# PC2CAN.net
KiCad netlist of a schematic drawn in EAGLE
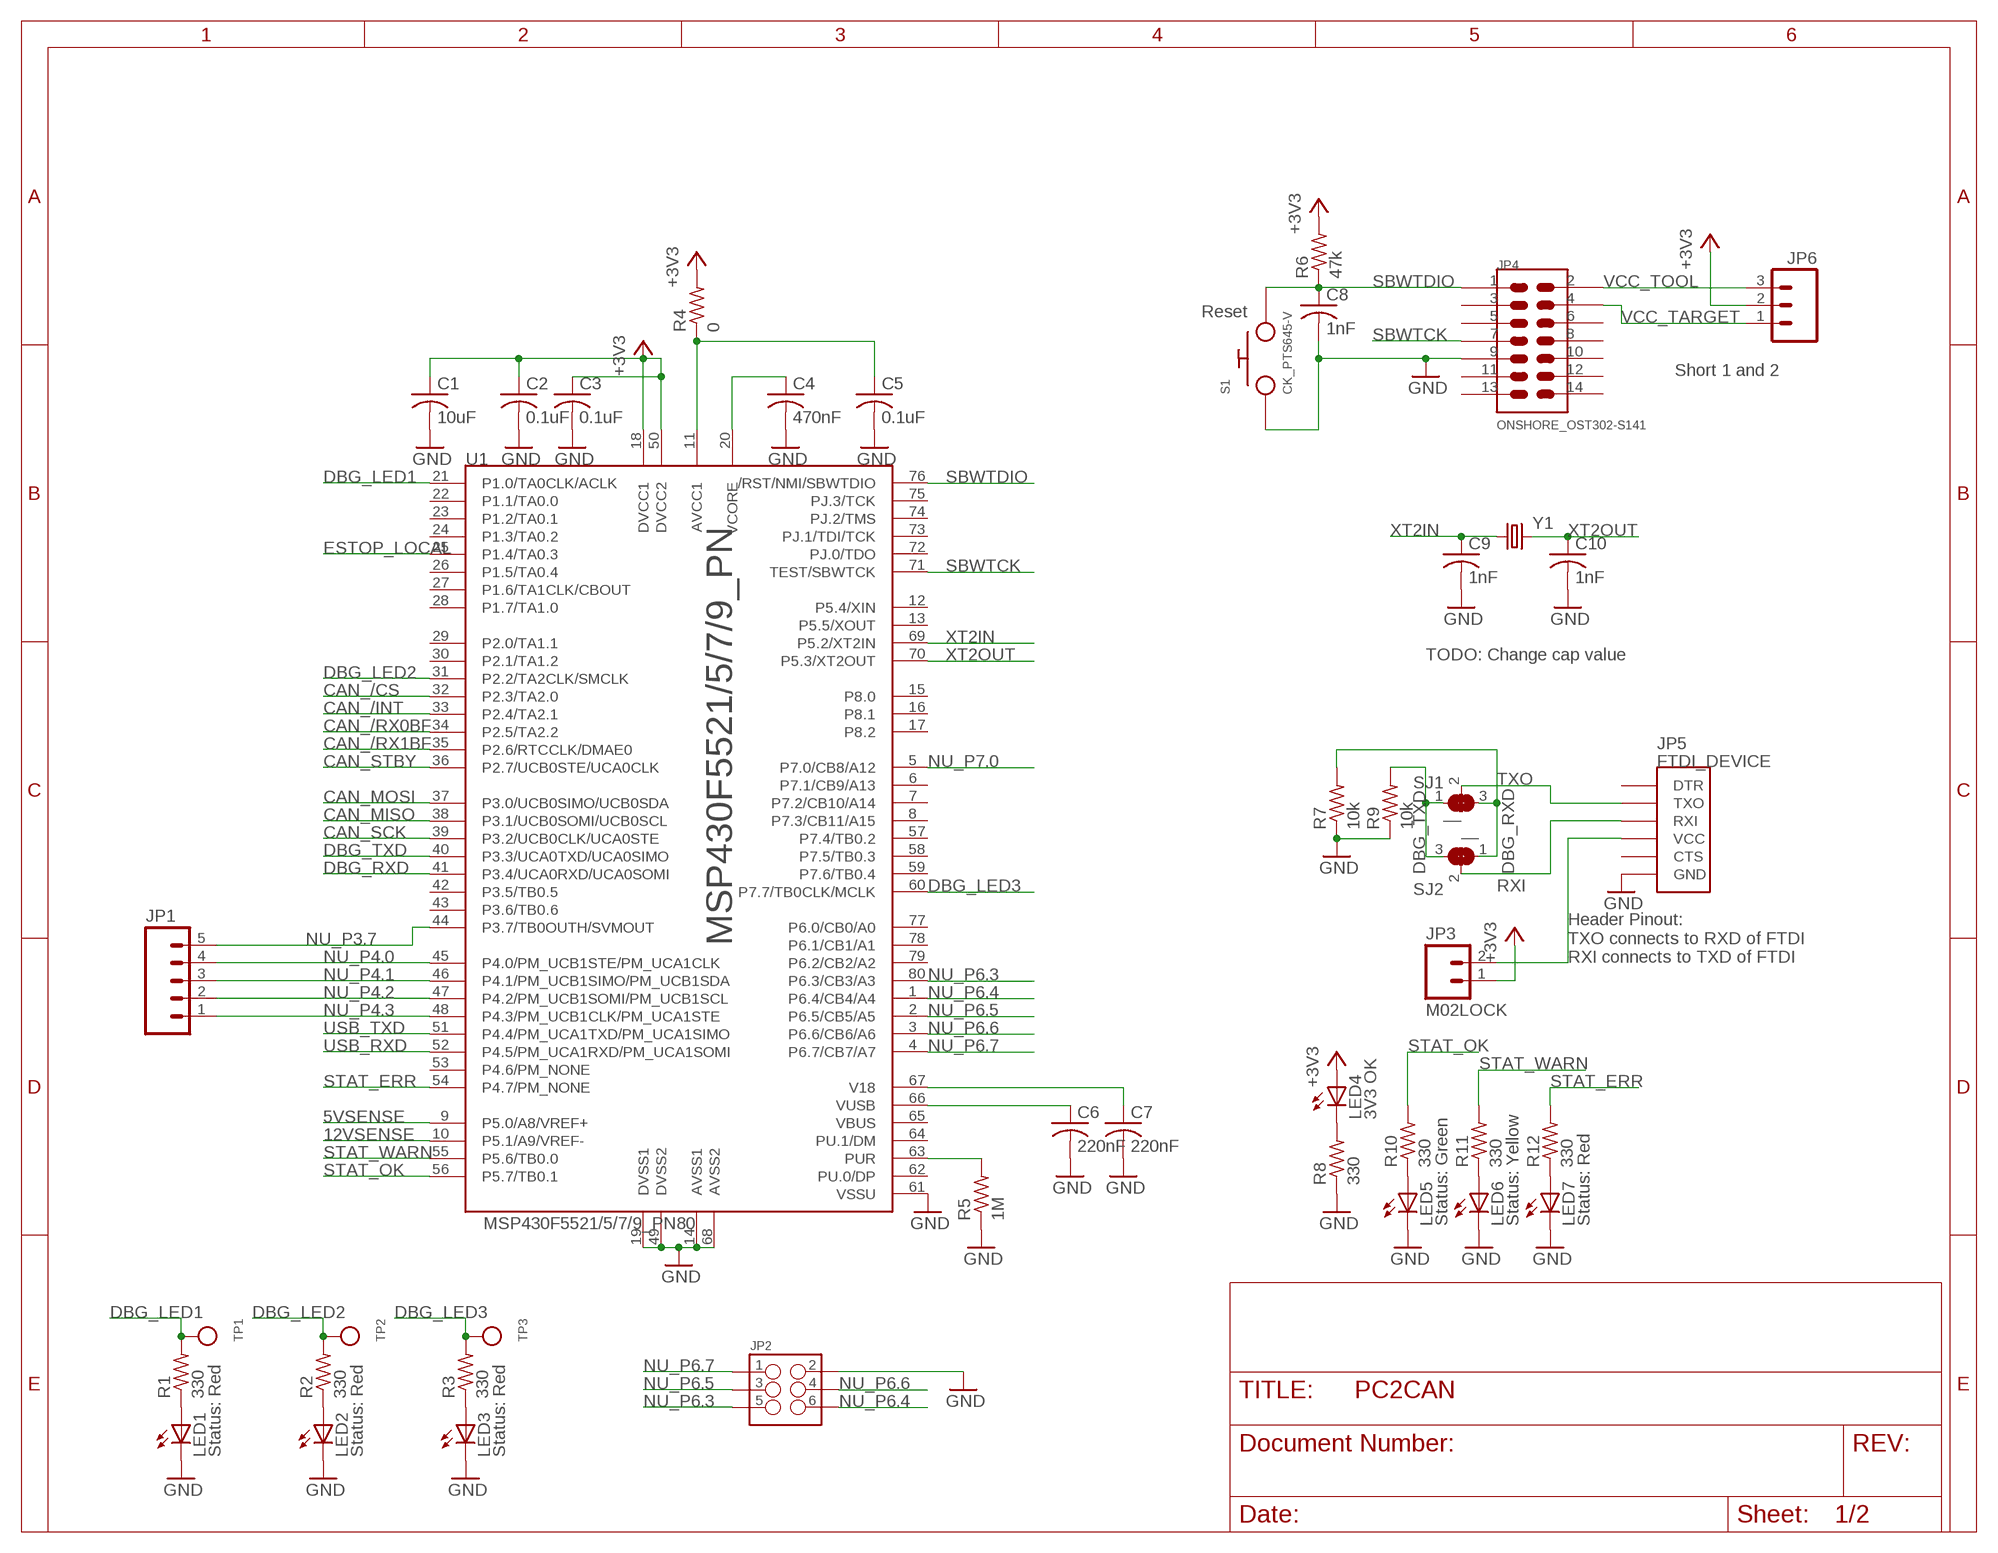
[diagram p0: schematic, sheet 1]
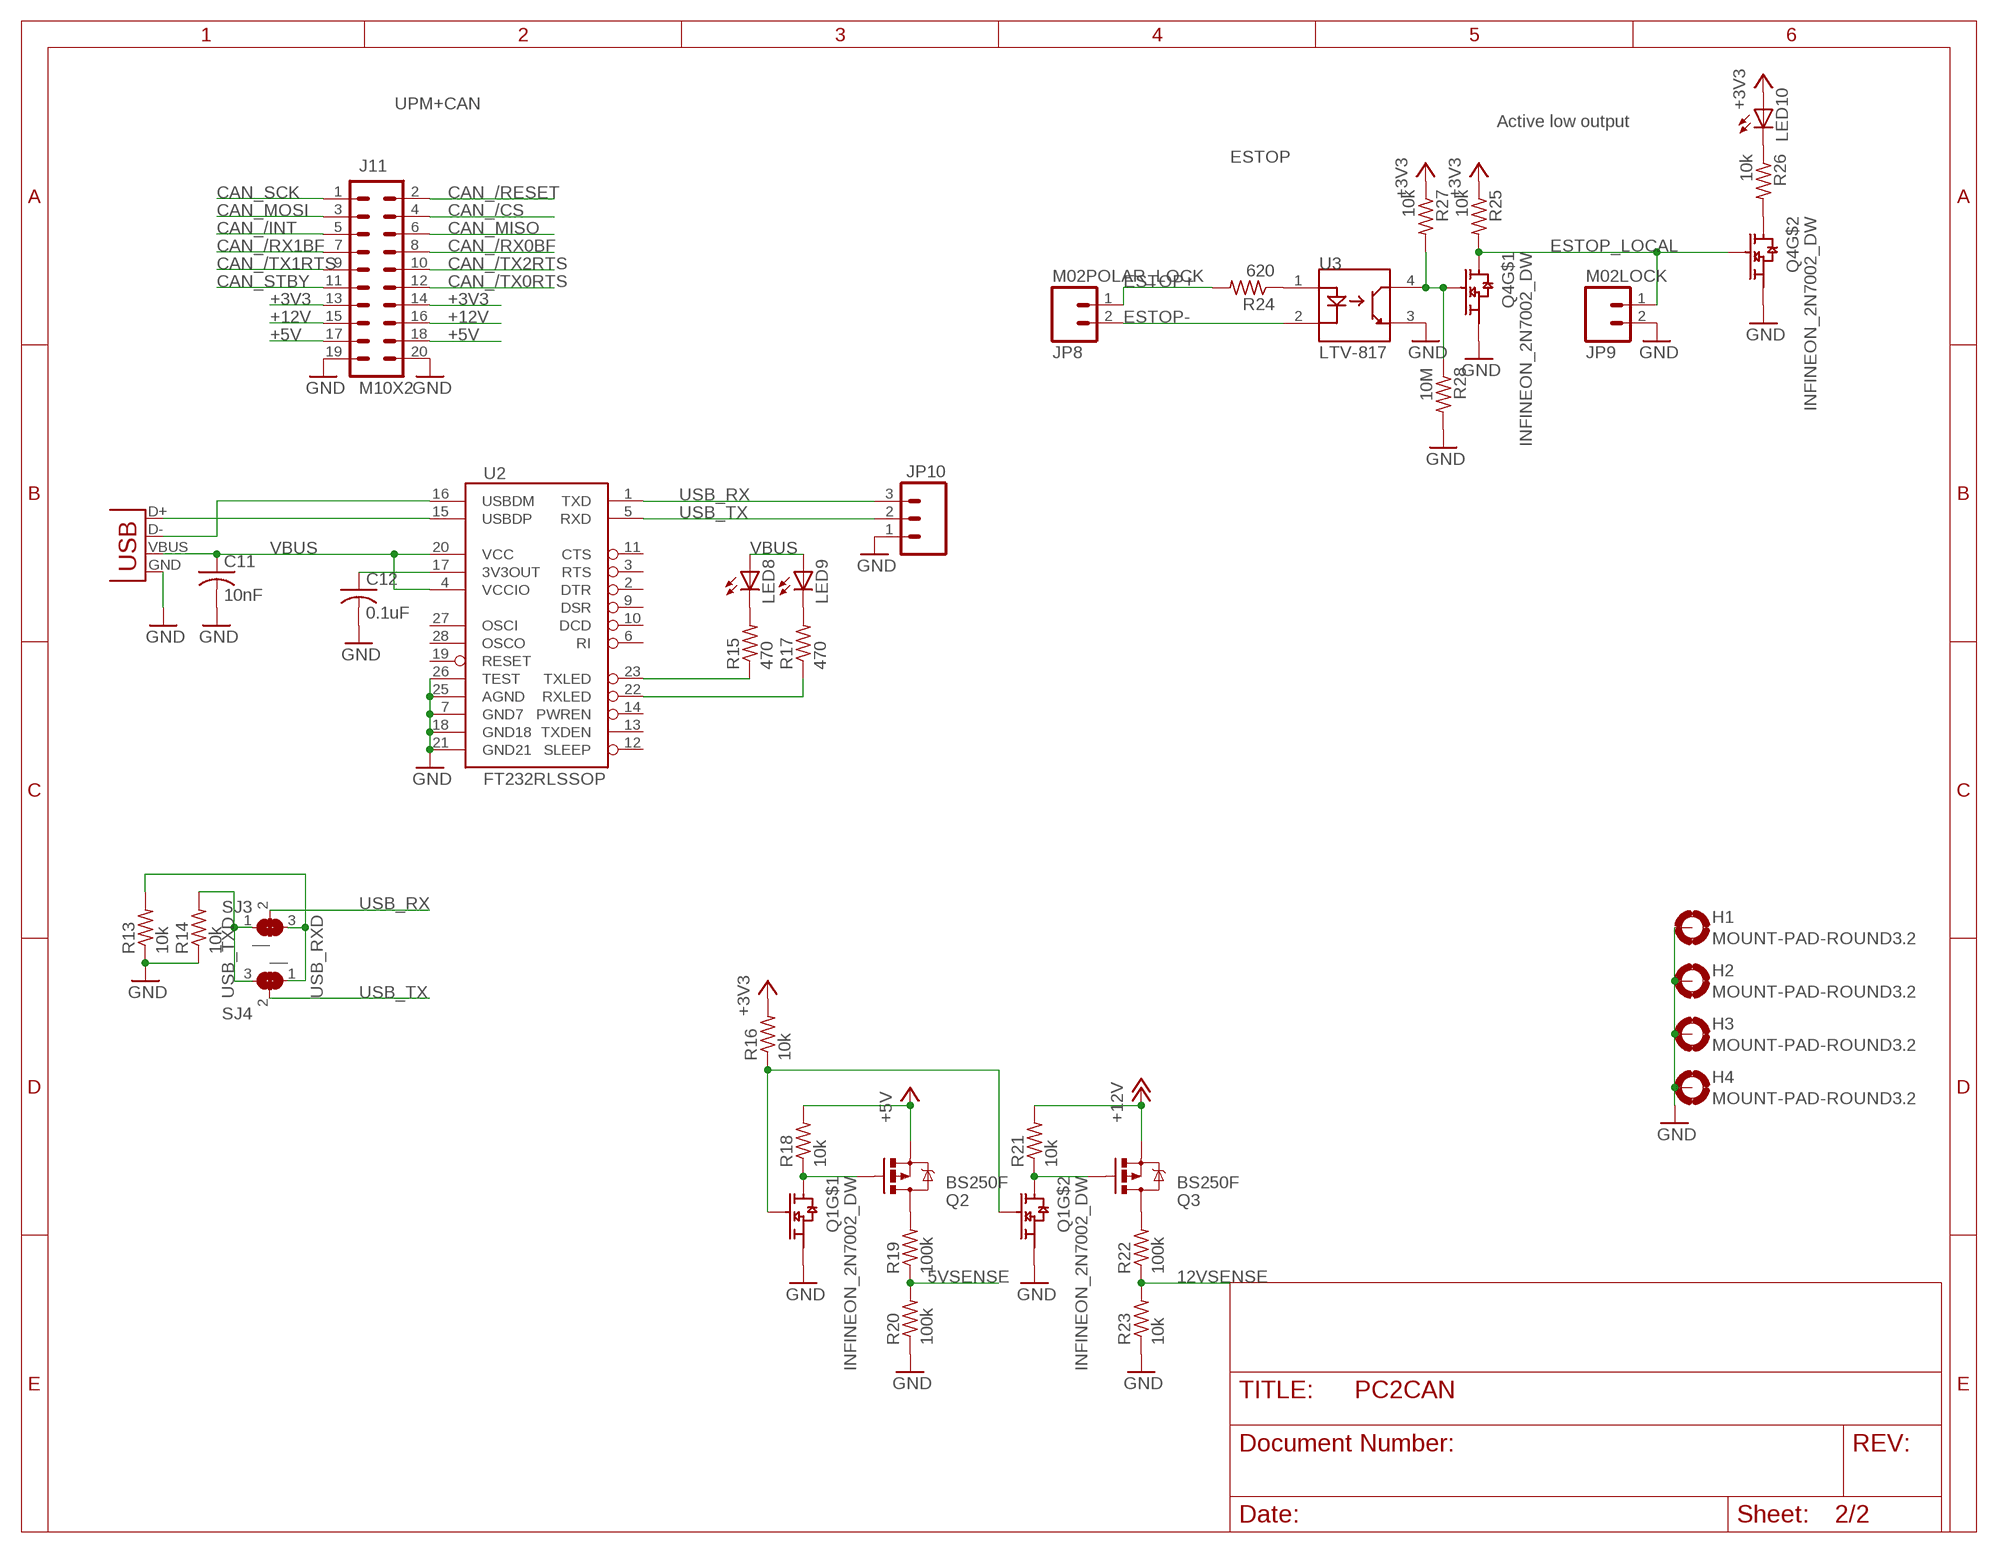
[diagram p1: schematic, sheet 2]

(export (version "E")
  (design (tool "Eeschema 10.0.6"))
  (components
    (comp (ref "C1")
      (value "10uF")
      (footprint "eagle-import:C0805")
      (libsource (lib "eagle-import") (part "C-USC0805"))
    )
    (comp (ref "C2")
      (value "0.1uF")
      (footprint "eagle-import:C0603")
      (libsource (lib "eagle-import") (part "C-USC0603"))
    )
    (comp (ref "C3")
      (value "0.1uF")
      (footprint "eagle-import:C0603")
      (libsource (lib "eagle-import") (part "C-USC0603"))
    )
    (comp (ref "C4")
      (value "470nF")
      (footprint "eagle-import:C0603")
      (libsource (lib "eagle-import") (part "C-USC0603"))
    )
    (comp (ref "C5")
      (value "0.1uF")
      (footprint "eagle-import:C0603")
      (libsource (lib "eagle-import") (part "C-USC0603"))
    )
    (comp (ref "C6")
      (value "220nF")
      (footprint "eagle-import:C0603")
      (libsource (lib "eagle-import") (part "C-USC0603"))
    )
    (comp (ref "C7")
      (value "220nF")
      (footprint "eagle-import:C0603")
      (libsource (lib "eagle-import") (part "C-USC0603"))
    )
    (comp (ref "C8")
      (value "1nF")
      (footprint "eagle-import:C0603")
      (libsource (lib "eagle-import") (part "C-USC0603"))
    )
    (comp (ref "C9")
      (value "1nF")
      (footprint "eagle-import:C0603")
      (libsource (lib "eagle-import") (part "C-USC0603"))
    )
    (comp (ref "C10")
      (value "1nF")
      (footprint "eagle-import:C0603")
      (libsource (lib "eagle-import") (part "C-USC0603"))
    )
    (comp (ref "JP1")
      (value "M05PTH")
      (footprint "eagle-import:1X05")
      (libsource (lib "eagle-import") (part "M05PTH"))
    )
    (comp (ref "JP2")
      (value "M03X22X3_SILK_SM")
      (footprint "eagle-import:2X3")
      (libsource (lib "eagle-import") (part "M03X22X3_SILK_SM"))
    )
    (comp (ref "JP3")
      (value "M02LOCK")
      (footprint "eagle-import:1X02_LOCK")
      (libsource (lib "eagle-import") (part "M02LOCK"))
    )
    (comp (ref "JP4")
      (value "ONSHORE_OST302-S141")
      (footprint "eagle-import:ONSHORE_OST302-S141")
      (libsource (lib "eagle-import") (part "ONSHORE_OST302-S141"))
    )
    (comp (ref "JP5")
      (value "FTDI_DEVICE")
      (footprint "eagle-import:FTDI_DEVICE_SIDE")
      (libsource (lib "eagle-import") (part "FTDI_DEVICE"))
    )
    (comp (ref "JP6")
      (value "M03LOCK")
      (footprint "eagle-import:1X03_LOCK")
      (libsource (lib "eagle-import") (part "M03LOCK"))
    )
    (comp (ref "LED1")
      (value "Status: Red")
      (footprint "eagle-import:LED-0603")
      (libsource (lib "eagle-import") (part "LED0603"))
    )
    (comp (ref "LED2")
      (value "Status: Red")
      (footprint "eagle-import:LED-0603")
      (libsource (lib "eagle-import") (part "LED0603"))
    )
    (comp (ref "LED3")
      (value "Status: Red")
      (footprint "eagle-import:LED-0603")
      (libsource (lib "eagle-import") (part "LED0603"))
    )
    (comp (ref "LED4")
      (value "3V3 OK")
      (footprint "eagle-import:LED-0603")
      (libsource (lib "eagle-import") (part "LED0603"))
    )
    (comp (ref "LED5")
      (value "Status: Green")
      (footprint "eagle-import:LED-0603")
      (libsource (lib "eagle-import") (part "LED0603"))
    )
    (comp (ref "LED6")
      (value "Status: Yellow")
      (footprint "eagle-import:LED-0603")
      (libsource (lib "eagle-import") (part "LED0603"))
    )
    (comp (ref "LED7")
      (value "Status: Red")
      (footprint "eagle-import:LED-0603")
      (libsource (lib "eagle-import") (part "LED0603"))
    )
    (comp (ref "R1")
      (value "330")
      (footprint "eagle-import:R0603")
      (libsource (lib "eagle-import") (part "R-US_R0603"))
    )
    (comp (ref "R2")
      (value "330")
      (footprint "eagle-import:R0603")
      (libsource (lib "eagle-import") (part "R-US_R0603"))
    )
    (comp (ref "R3")
      (value "330")
      (footprint "eagle-import:R0603")
      (libsource (lib "eagle-import") (part "R-US_R0603"))
    )
    (comp (ref "R4")
      (value "0")
      (footprint "eagle-import:R0603")
      (libsource (lib "eagle-import") (part "R-US_R0603"))
    )
    (comp (ref "R5")
      (value "1M")
      (footprint "eagle-import:R0603")
      (libsource (lib "eagle-import") (part "R-US_R0603"))
    )
    (comp (ref "R6")
      (value "47k")
      (footprint "eagle-import:R0603")
      (libsource (lib "eagle-import") (part "R-US_R0603"))
    )
    (comp (ref "R7")
      (value "10k")
      (footprint "eagle-import:R0603")
      (libsource (lib "eagle-import") (part "R-US_R0603"))
    )
    (comp (ref "R8")
      (value "330")
      (footprint "eagle-import:R0603")
      (libsource (lib "eagle-import") (part "R-US_R0603"))
    )
    (comp (ref "R9")
      (value "10k")
      (footprint "eagle-import:R0603")
      (libsource (lib "eagle-import") (part "R-US_R0603"))
    )
    (comp (ref "R10")
      (value "330")
      (footprint "eagle-import:R0603")
      (libsource (lib "eagle-import") (part "R-US_R0603"))
    )
    (comp (ref "R11")
      (value "330")
      (footprint "eagle-import:R0603")
      (libsource (lib "eagle-import") (part "R-US_R0603"))
    )
    (comp (ref "R12")
      (value "330")
      (footprint "eagle-import:R0603")
      (libsource (lib "eagle-import") (part "R-US_R0603"))
    )
    (comp (ref "S1")
      (value "CK_PTS645-V")
      (footprint "eagle-import:CK_PTS645-V")
      (libsource (lib "eagle-import") (part "CK_PTS645-V"))
    )
    (comp (ref "SJ1")
      (value "SOLDERJUMPER_2WAY0603")
      (footprint "eagle-import:SOLDERJUMPER_2WAY_OPEN_0603")
      (libsource (lib "eagle-import") (part "SOLDERJUMPER_2WAY0603"))
    )
    (comp (ref "SJ2")
      (value "SOLDERJUMPER_2WAY0603")
      (footprint "eagle-import:SOLDERJUMPER_2WAY_OPEN_0603")
      (libsource (lib "eagle-import") (part "SOLDERJUMPER_2WAY0603"))
    )
    (comp (ref "TP1")
      (value "TESTPOINT0.1\"")
      (footprint "eagle-import:1X01_ROUND")
      (libsource (lib "eagle-import") (part "TESTPOINT0.1{dblquote}"))
    )
    (comp (ref "TP2")
      (value "TESTPOINT0.1\"")
      (footprint "eagle-import:1X01_ROUND")
      (libsource (lib "eagle-import") (part "TESTPOINT0.1{dblquote}"))
    )
    (comp (ref "TP3")
      (value "TESTPOINT0.1\"")
      (footprint "eagle-import:1X01_ROUND")
      (libsource (lib "eagle-import") (part "TESTPOINT0.1{dblquote}"))
    )
    (comp (ref "U1")
      (value "MSP430F5521/5/7/9_PN80")
      (footprint "eagle-import:PN80")
      (libsource (lib "eagle-import") (part "MSP430F5521/5/7/9_PN80"))
    )
    (comp (ref "Y1")
      (value "CRYSTALHC49UV")
      (footprint "eagle-import:HC49U-V")
      (libsource (lib "eagle-import") (part "CRYSTALHC49UV"))
    )
    (comp (ref "C11")
      (value "10nF")
      (footprint "eagle-import:C0603")
      (libsource (lib "eagle-import") (part "C-USC0603"))
    )
    (comp (ref "C12")
      (value "0.1uF")
      (footprint "eagle-import:C0603")
      (libsource (lib "eagle-import") (part "C-USC0603"))
    )
    (comp (ref "H1")
      (value "MOUNT-PAD-ROUND3.2")
      (footprint "eagle-import:3,2-PAD")
      (libsource (lib "eagle-import") (part "MOUNT-PAD-ROUND3.2"))
    )
    (comp (ref "H2")
      (value "MOUNT-PAD-ROUND3.2")
      (footprint "eagle-import:3,2-PAD")
      (libsource (lib "eagle-import") (part "MOUNT-PAD-ROUND3.2"))
    )
    (comp (ref "H3")
      (value "MOUNT-PAD-ROUND3.2")
      (footprint "eagle-import:3,2-PAD")
      (libsource (lib "eagle-import") (part "MOUNT-PAD-ROUND3.2"))
    )
    (comp (ref "H4")
      (value "MOUNT-PAD-ROUND3.2")
      (footprint "eagle-import:3,2-PAD")
      (libsource (lib "eagle-import") (part "MOUNT-PAD-ROUND3.2"))
    )
    (comp (ref "J11")
      (value "M10X2")
      (footprint "eagle-import:2X10")
      (libsource (lib "eagle-import") (part "M10X2"))
    )
    (comp (ref "JP7")
      (value "USB-B")
      (footprint "eagle-import:USB-B-PTH")
      (libsource (lib "eagle-import") (part "USBPTH"))
    )
    (comp (ref "JP8")
      (value "M02POLAR_LOCK")
      (footprint "eagle-import:MOLEX-1X2_LOCK")
      (libsource (lib "eagle-import") (part "M02POLAR_LOCK"))
    )
    (comp (ref "JP9")
      (value "M02LOCK")
      (footprint "eagle-import:1X02_LOCK")
      (libsource (lib "eagle-import") (part "M02LOCK"))
    )
    (comp (ref "JP10")
      (value "M03LOCK")
      (footprint "eagle-import:1X03_LOCK")
      (libsource (lib "eagle-import") (part "M03LOCK"))
    )
    (comp (ref "LED8")
      (value "LED0603")
      (footprint "eagle-import:LED-0603")
      (libsource (lib "eagle-import") (part "LED0603"))
    )
    (comp (ref "LED9")
      (value "LED0603")
      (footprint "eagle-import:LED-0603")
      (libsource (lib "eagle-import") (part "LED0603"))
    )
    (comp (ref "LED10")
      (value "LED0603")
      (footprint "eagle-import:LED-0603")
      (libsource (lib "eagle-import") (part "LED0603"))
    )
    (comp (ref "Q1")
      (value "INFINEON_2N7002_DW")
      (footprint "eagle-import:INFINEON_SOT363")
      (libsource (lib "eagle-import") (part "INFINEON_2N7002_DW"))
    )
    (comp (ref "Q2")
      (value "BS250F")
      (footprint "eagle-import:SOT23-3")
      (libsource (lib "eagle-import") (part "MOSFET-PCHANNELSMD"))
    )
    (comp (ref "Q3")
      (value "BS250F")
      (footprint "eagle-import:SOT23-3")
      (libsource (lib "eagle-import") (part "MOSFET-PCHANNELSMD"))
    )
    (comp (ref "Q4")
      (value "INFINEON_2N7002_DW")
      (footprint "eagle-import:INFINEON_SOT363")
      (libsource (lib "eagle-import") (part "INFINEON_2N7002_DW"))
    )
    (comp (ref "R13")
      (value "10k")
      (footprint "eagle-import:R0603")
      (libsource (lib "eagle-import") (part "R-US_R0603"))
    )
    (comp (ref "R14")
      (value "10k")
      (footprint "eagle-import:R0603")
      (libsource (lib "eagle-import") (part "R-US_R0603"))
    )
    (comp (ref "R15")
      (value "470")
      (footprint "eagle-import:R0603")
      (libsource (lib "eagle-import") (part "R-US_R0603"))
    )
    (comp (ref "R16")
      (value "10k")
      (footprint "eagle-import:R0603")
      (libsource (lib "eagle-import") (part "R-US_R0603"))
    )
    (comp (ref "R17")
      (value "470")
      (footprint "eagle-import:R0603")
      (libsource (lib "eagle-import") (part "R-US_R0603"))
    )
    (comp (ref "R18")
      (value "10k")
      (footprint "eagle-import:R0603")
      (libsource (lib "eagle-import") (part "R-US_R0603"))
    )
    (comp (ref "R19")
      (value "100k")
      (footprint "eagle-import:R0603")
      (libsource (lib "eagle-import") (part "R-US_R0603"))
    )
    (comp (ref "R20")
      (value "100k")
      (footprint "eagle-import:R0603")
      (libsource (lib "eagle-import") (part "R-US_R0603"))
    )
    (comp (ref "R21")
      (value "10k")
      (footprint "eagle-import:R0603")
      (libsource (lib "eagle-import") (part "R-US_R0603"))
    )
    (comp (ref "R22")
      (value "100k")
      (footprint "eagle-import:R0603")
      (libsource (lib "eagle-import") (part "R-US_R0603"))
    )
    (comp (ref "R23")
      (value "10k")
      (footprint "eagle-import:R0603")
      (libsource (lib "eagle-import") (part "R-US_R0603"))
    )
    (comp (ref "R24")
      (value "620")
      (footprint "eagle-import:R0603")
      (libsource (lib "eagle-import") (part "R-US_R0603"))
    )
    (comp (ref "R25")
      (value "10k")
      (footprint "eagle-import:R0603")
      (libsource (lib "eagle-import") (part "R-US_R0603"))
    )
    (comp (ref "R26")
      (value "10k")
      (footprint "eagle-import:R0603")
      (libsource (lib "eagle-import") (part "R-US_R0603"))
    )
    (comp (ref "R27")
      (value "10k")
      (footprint "eagle-import:R0603")
      (libsource (lib "eagle-import") (part "R-US_R0603"))
    )
    (comp (ref "R28")
      (value "10M")
      (footprint "eagle-import:R0603")
      (libsource (lib "eagle-import") (part "R-US_R0603"))
    )
    (comp (ref "SJ3")
      (value "SOLDERJUMPER_2WAY0603")
      (footprint "eagle-import:SOLDERJUMPER_2WAY_OPEN_0603")
      (libsource (lib "eagle-import") (part "SOLDERJUMPER_2WAY0603"))
    )
    (comp (ref "SJ4")
      (value "SOLDERJUMPER_2WAY0603")
      (footprint "eagle-import:SOLDERJUMPER_2WAY_OPEN_0603")
      (libsource (lib "eagle-import") (part "SOLDERJUMPER_2WAY0603"))
    )
    (comp (ref "U2")
      (value "FT232RLSSOP")
      (footprint "eagle-import:SSOP28DB")
      (libsource (lib "eagle-import") (part "FT232RLSSOP"))
    )
    (comp (ref "U3")
      (value "LTV-817")
      (footprint "eagle-import:LITEON_DIL04_.3")
      (libsource (lib "eagle-import") (part "LTV-817"))
    )
  )
  (nets
    (net (code "1") (name "+3V3") (class "Default")
      (node (ref "C1") (pin "1") (pinfunction "1_1") (pintype "passive"))
      (node (ref "C2") (pin "1") (pinfunction "1_1") (pintype "passive"))
      (node (ref "C3") (pin "1") (pinfunction "1_1") (pintype "passive"))
      (node (ref "J11") (pin "13") (pinfunction "13_13") (pintype "passive"))
      (node (ref "J11") (pin "14") (pinfunction "14_14") (pintype "passive"))
      (node (ref "JP3") (pin "1") (pinfunction "1_1") (pintype "passive"))
      (node (ref "JP6") (pin "2") (pinfunction "2_2") (pintype "passive"))
      (node (ref "LED10") (pin "A") (pinfunction "A_A") (pintype "passive"))
      (node (ref "LED4") (pin "A") (pinfunction "A_A") (pintype "passive"))
      (node (ref "R16") (pin "2") (pinfunction "2_2") (pintype "passive"))
      (node (ref "R25") (pin "1") (pinfunction "1_1") (pintype "passive"))
      (node (ref "R27") (pin "1") (pinfunction "1_1") (pintype "passive"))
      (node (ref "R4") (pin "2") (pinfunction "2_2") (pintype "passive"))
      (node (ref "R6") (pin "2") (pinfunction "2_2") (pintype "passive"))
      (node (ref "U1") (pin "18") (pinfunction "DVCC1_18") (pintype "bidirectional"))
      (node (ref "U1") (pin "50") (pinfunction "DVCC2_50") (pintype "bidirectional"))
    )
    (net (code "2") (name "+5V") (class "Default")
      (node (ref "J11") (pin "17") (pinfunction "17_17") (pintype "passive"))
      (node (ref "J11") (pin "18") (pinfunction "18_18") (pintype "passive"))
      (node (ref "Q2") (pin "2") (pinfunction "S_2") (pintype "passive"))
      (node (ref "R18") (pin "2") (pinfunction "2_2") (pintype "passive"))
    )
    (net (code "3") (name "+12V") (class "Default")
      (node (ref "J11") (pin "15") (pinfunction "15_15") (pintype "passive"))
      (node (ref "J11") (pin "16") (pinfunction "16_16") (pintype "passive"))
      (node (ref "Q3") (pin "2") (pinfunction "S_2") (pintype "passive"))
      (node (ref "R21") (pin "2") (pinfunction "2_2") (pintype "passive"))
    )
    (net (code "4") (name "5VSENSE") (class "Default")
      (node (ref "R19") (pin "1") (pinfunction "1_1") (pintype "passive"))
      (node (ref "R20") (pin "2") (pinfunction "2_2") (pintype "passive"))
      (node (ref "U1") (pin "9") (pinfunction "P5.0/A8/VREF+_9") (pintype "bidirectional"))
    )
    (net (code "5") (name "12VSENSE") (class "Default")
      (node (ref "R22") (pin "1") (pinfunction "1_1") (pintype "passive"))
      (node (ref "R23") (pin "2") (pinfunction "2_2") (pintype "passive"))
      (node (ref "U1") (pin "10") (pinfunction "P5.1/A9/VREF-_10") (pintype "bidirectional"))
    )
    (net (code "6") (name "CAN_MISO") (class "Default")
      (node (ref "J11") (pin "6") (pinfunction "6_6") (pintype "passive"))
      (node (ref "U1") (pin "38") (pinfunction "P3.1/UCB0SOMI/UCB0SCL_38") (pintype "bidirectional"))
    )
    (net (code "7") (name "CAN_MOSI") (class "Default")
      (node (ref "J11") (pin "3") (pinfunction "3_3") (pintype "passive"))
      (node (ref "U1") (pin "37") (pinfunction "P3.0/UCB0SIMO/UCB0SDA_37") (pintype "bidirectional"))
    )
    (net (code "8") (name "CAN_SCK") (class "Default")
      (node (ref "J11") (pin "1") (pinfunction "1_1") (pintype "passive"))
      (node (ref "U1") (pin "39") (pinfunction "P3.2/UCB0CLK/UCA0STE_39") (pintype "bidirectional"))
    )
    (net (code "9") (name "CAN_STBY") (class "Default")
      (node (ref "J11") (pin "11") (pinfunction "11_11") (pintype "passive"))
      (node (ref "U1") (pin "36") (pinfunction "P2.7/UCB0STE/UCA0CLK_36") (pintype "bidirectional"))
    )
    (net (code "10") (name "CAN_{slash}CS") (class "Default")
      (node (ref "J11") (pin "4") (pinfunction "4_4") (pintype "passive"))
      (node (ref "U1") (pin "32") (pinfunction "P2.3/TA2.0_32") (pintype "bidirectional"))
    )
    (net (code "11") (name "CAN_{slash}INT") (class "Default")
      (node (ref "J11") (pin "5") (pinfunction "5_5") (pintype "passive"))
      (node (ref "U1") (pin "33") (pinfunction "P2.4/TA2.1_33") (pintype "bidirectional"))
    )
    (net (code "12") (name "CAN_{slash}RESET") (class "Default")
      (node (ref "J11") (pin "2") (pinfunction "2_2") (pintype "passive"))
    )
    (net (code "13") (name "CAN_{slash}RX0BF") (class "Default")
      (node (ref "J11") (pin "8") (pinfunction "8_8") (pintype "passive"))
      (node (ref "U1") (pin "34") (pinfunction "P2.5/TA2.2_34") (pintype "bidirectional"))
    )
    (net (code "14") (name "CAN_{slash}RX1BF") (class "Default")
      (node (ref "J11") (pin "7") (pinfunction "7_7") (pintype "passive"))
      (node (ref "U1") (pin "35") (pinfunction "P2.6/RTCCLK/DMAE0_35") (pintype "bidirectional"))
    )
    (net (code "15") (name "CAN_{slash}TX0RTS") (class "Default")
      (node (ref "J11") (pin "12") (pinfunction "12_12") (pintype "passive"))
    )
    (net (code "16") (name "CAN_{slash}TX1RTS") (class "Default")
      (node (ref "J11") (pin "9") (pinfunction "9_9") (pintype "passive"))
    )
    (net (code "17") (name "CAN_{slash}TX2RTS") (class "Default")
      (node (ref "J11") (pin "10") (pinfunction "10_10") (pintype "passive"))
    )
    (net (code "18") (name "DBG_LED1") (class "Default")
      (node (ref "R1") (pin "2") (pinfunction "2_2") (pintype "passive"))
      (node (ref "TP1") (pin "1") (pinfunction "P$1_1") (pintype "bidirectional"))
      (node (ref "U1") (pin "21") (pinfunction "P1.0/TA0CLK/ACLK_21") (pintype "bidirectional"))
    )
    (net (code "19") (name "DBG_LED2") (class "Default")
      (node (ref "R2") (pin "2") (pinfunction "2_2") (pintype "passive"))
      (node (ref "TP2") (pin "1") (pinfunction "P$1_1") (pintype "bidirectional"))
      (node (ref "U1") (pin "31") (pinfunction "P2.2/TA2CLK/SMCLK_31") (pintype "bidirectional"))
    )
    (net (code "20") (name "DBG_LED3") (class "Default")
      (node (ref "R3") (pin "2") (pinfunction "2_2") (pintype "passive"))
      (node (ref "TP3") (pin "1") (pinfunction "P$1_1") (pintype "bidirectional"))
      (node (ref "U1") (pin "60") (pinfunction "P7.7/TB0CLK/MCLK_60") (pintype "bidirectional"))
    )
    (net (code "21") (name "DBG_RXD") (class "Default")
      (node (ref "R7") (pin "2") (pinfunction "2_2") (pintype "passive"))
      (node (ref "SJ1") (pin "3") (pinfunction "3_3") (pintype "passive"))
      (node (ref "SJ2") (pin "1") (pinfunction "1_1") (pintype "passive"))
      (node (ref "U1") (pin "41") (pinfunction "P3.4/UCA0RXD/UCA0SOMI_41") (pintype "bidirectional"))
    )
    (net (code "22") (name "DBG_TXD") (class "Default")
      (node (ref "R9") (pin "2") (pinfunction "2_2") (pintype "passive"))
      (node (ref "SJ1") (pin "1") (pinfunction "1_1") (pintype "passive"))
      (node (ref "SJ2") (pin "3") (pinfunction "3_3") (pintype "passive"))
      (node (ref "U1") (pin "40") (pinfunction "P3.3/UCA0TXD/UCA0SIMO_40") (pintype "bidirectional"))
    )
    (net (code "23") (name "ESTOP+") (class "Default")
      (node (ref "JP8") (pin "1") (pinfunction "1_1") (pintype "passive"))
      (node (ref "R24") (pin "2") (pinfunction "2_2") (pintype "passive"))
    )
    (net (code "24") (name "ESTOP-") (class "Default")
      (node (ref "JP8") (pin "2") (pinfunction "2_2") (pintype "passive"))
      (node (ref "U3") (pin "2") (pinfunction "2_2") (pintype "bidirectional"))
    )
    (net (code "25") (name "ESTOP_LOCAL") (class "Default")
      (node (ref "JP9") (pin "1") (pinfunction "1_1") (pintype "passive"))
      (node (ref "Q4") (pin "5") (pinfunction "GATE_5") (pintype "bidirectional"))
      (node (ref "Q4") (pin "6") (pinfunction "DRAIN_6") (pintype "bidirectional"))
      (node (ref "R25") (pin "2") (pinfunction "2_2") (pintype "passive"))
      (node (ref "U1") (pin "25") (pinfunction "P1.4/TA0.3_25") (pintype "bidirectional"))
    )
    (net (code "26") (name "GND") (class "Default")
      (node (ref "C1") (pin "2") (pinfunction "2_2") (pintype "passive"))
      (node (ref "C10") (pin "2") (pinfunction "2_2") (pintype "passive"))
      (node (ref "C11") (pin "2") (pinfunction "2_2") (pintype "passive"))
      (node (ref "C12") (pin "2") (pinfunction "2_2") (pintype "passive"))
      (node (ref "C2") (pin "2") (pinfunction "2_2") (pintype "passive"))
      (node (ref "C3") (pin "2") (pinfunction "2_2") (pintype "passive"))
      (node (ref "C4") (pin "2") (pinfunction "2_2") (pintype "passive"))
      (node (ref "C5") (pin "2") (pinfunction "2_2") (pintype "passive"))
      (node (ref "C6") (pin "2") (pinfunction "2_2") (pintype "passive"))
      (node (ref "C7") (pin "2") (pinfunction "2_2") (pintype "passive"))
      (node (ref "C8") (pin "2") (pinfunction "2_2") (pintype "passive"))
      (node (ref "C9") (pin "2") (pinfunction "2_2") (pintype "passive"))
      (node (ref "H1") (pin "B3,2") (pinfunction "MOUNT_B3,2") (pintype "passive"))
      (node (ref "H2") (pin "B3,2") (pinfunction "MOUNT_B3,2") (pintype "passive"))
      (node (ref "H3") (pin "B3,2") (pinfunction "MOUNT_B3,2") (pintype "passive"))
      (node (ref "H4") (pin "B3,2") (pinfunction "MOUNT_B3,2") (pintype "passive"))
      (node (ref "J11") (pin "19") (pinfunction "19_19") (pintype "passive"))
      (node (ref "J11") (pin "20") (pinfunction "20_20") (pintype "passive"))
      (node (ref "JP10") (pin "1") (pinfunction "1_1") (pintype "passive"))
      (node (ref "JP2") (pin "2") (pinfunction "2_2") (pintype "bidirectional"))
      (node (ref "JP4") (pin "9") (pinfunction "9_9") (pintype "bidirectional"))
      (node (ref "JP5") (pin "P$6") (pinfunction "GND_P$6") (pintype "bidirectional"))
      (node (ref "JP7") (pin "GND") (pinfunction "GND_GND") (pintype "bidirectional"))
      (node (ref "JP9") (pin "2") (pinfunction "2_2") (pintype "passive"))
      (node (ref "LED1") (pin "C") (pinfunction "C_C") (pintype "passive"))
      (node (ref "LED2") (pin "C") (pinfunction "C_C") (pintype "passive"))
      (node (ref "LED3") (pin "C") (pinfunction "C_C") (pintype "passive"))
      (node (ref "LED5") (pin "C") (pinfunction "C_C") (pintype "passive"))
      (node (ref "LED6") (pin "C") (pinfunction "C_C") (pintype "passive"))
      (node (ref "LED7") (pin "C") (pinfunction "C_C") (pintype "passive"))
      (node (ref "Q1") (pin "1") (pinfunction "SOURCE_1") (pintype "bidirectional"))
      (node (ref "Q1") (pin "4") (pinfunction "SOURCE_4") (pintype "bidirectional"))
      (node (ref "Q4") (pin "1") (pinfunction "SOURCE_1") (pintype "bidirectional"))
      (node (ref "Q4") (pin "4") (pinfunction "SOURCE_4") (pintype "bidirectional"))
      (node (ref "R13") (pin "1") (pinfunction "1_1") (pintype "passive"))
      (node (ref "R14") (pin "1") (pinfunction "1_1") (pintype "passive"))
      (node (ref "R20") (pin "1") (pinfunction "1_1") (pintype "passive"))
      (node (ref "R23") (pin "1") (pinfunction "1_1") (pintype "passive"))
      (node (ref "R28") (pin "2") (pinfunction "2_2") (pintype "passive"))
      (node (ref "R5") (pin "1") (pinfunction "1_1") (pintype "passive"))
      (node (ref "R7") (pin "1") (pinfunction "1_1") (pintype "passive"))
      (node (ref "R8") (pin "1") (pinfunction "1_1") (pintype "passive"))
      (node (ref "R9") (pin "1") (pinfunction "1_1") (pintype "passive"))
      (node (ref "S1") (pin "1") (pinfunction "1_1") (pintype "bidirectional"))
      (node (ref "U1") (pin "14") (pinfunction "AVSS1_14") (pintype "bidirectional"))
      (node (ref "U1") (pin "19") (pinfunction "DVSS1_19") (pintype "bidirectional"))
      (node (ref "U1") (pin "49") (pinfunction "DVSS2_49") (pintype "bidirectional"))
      (node (ref "U1") (pin "61") (pinfunction "VSSU_61") (pintype "bidirectional"))
      (node (ref "U1") (pin "68") (pinfunction "AVSS2_68") (pintype "bidirectional"))
      (node (ref "U2") (pin "18") (pinfunction "GND18_18") (pintype "power_in"))
      (node (ref "U2") (pin "21") (pinfunction "GND21_21") (pintype "power_in"))
      (node (ref "U2") (pin "25") (pinfunction "AGND_25") (pintype "power_in"))
      (node (ref "U2") (pin "26") (pinfunction "TEST_26") (pintype "input"))
      (node (ref "U2") (pin "7") (pinfunction "GND7_7") (pintype "power_in"))
      (node (ref "U3") (pin "3") (pinfunction "3_3") (pintype "bidirectional"))
    )
    (net (code "27") (name "NU_P3.7") (class "Default")
      (node (ref "JP1") (pin "5") (pinfunction "5_5") (pintype "passive"))
      (node (ref "U1") (pin "44") (pinfunction "P3.7/TB0OUTH/SVMOUT_44") (pintype "bidirectional"))
    )
    (net (code "28") (name "NU_P4.0") (class "Default")
      (node (ref "JP1") (pin "4") (pinfunction "4_4") (pintype "passive"))
      (node (ref "U1") (pin "45") (pinfunction "P4.0/PM_UCB1STE/PM_UCA1CLK_45") (pintype "bidirectional"))
    )
    (net (code "29") (name "NU_P4.1") (class "Default")
      (node (ref "JP1") (pin "3") (pinfunction "3_3") (pintype "passive"))
      (node (ref "U1") (pin "46") (pinfunction "P4.1/PM_UCB1SIMO/PM_UCB1SDA_46") (pintype "bidirectional"))
    )
    (net (code "30") (name "NU_P4.2") (class "Default")
      (node (ref "JP1") (pin "2") (pinfunction "2_2") (pintype "passive"))
      (node (ref "U1") (pin "47") (pinfunction "P4.2/PM_UCB1SOMI/PM_UCB1SCL_47") (pintype "bidirectional"))
    )
    (net (code "31") (name "NU_P4.3") (class "Default")
      (node (ref "JP1") (pin "1") (pinfunction "1_1") (pintype "passive"))
      (node (ref "U1") (pin "48") (pinfunction "P4.3/PM_UCB1CLK/PM_UCA1STE_48") (pintype "bidirectional"))
    )
    (net (code "32") (name "NU_P6.3") (class "Default")
      (node (ref "JP2") (pin "5") (pinfunction "5_5") (pintype "bidirectional"))
      (node (ref "U1") (pin "80") (pinfunction "P6.3/CB3/A3_80") (pintype "bidirectional"))
    )
    (net (code "33") (name "NU_P6.4") (class "Default")
      (node (ref "JP2") (pin "6") (pinfunction "6_6") (pintype "bidirectional"))
      (node (ref "U1") (pin "1") (pinfunction "P6.4/CB4/A4_1") (pintype "bidirectional"))
    )
    (net (code "34") (name "NU_P6.5") (class "Default")
      (node (ref "JP2") (pin "3") (pinfunction "3_3") (pintype "bidirectional"))
      (node (ref "U1") (pin "2") (pinfunction "P6.5/CB5/A5_2") (pintype "bidirectional"))
    )
    (net (code "35") (name "NU_P6.6") (class "Default")
      (node (ref "JP2") (pin "4") (pinfunction "4_4") (pintype "bidirectional"))
      (node (ref "U1") (pin "3") (pinfunction "P6.6/CB6/A6_3") (pintype "bidirectional"))
    )
    (net (code "36") (name "NU_P6.7") (class "Default")
      (node (ref "JP2") (pin "1") (pinfunction "1_1") (pintype "bidirectional"))
      (node (ref "U1") (pin "4") (pinfunction "P6.7/CB7/A7_4") (pintype "bidirectional"))
    )
    (net (code "37") (name "NU_P7.0") (class "Default")
      (node (ref "U1") (pin "5") (pinfunction "P7.0/CB8/A12_5") (pintype "bidirectional"))
    )
    (net (code "38") (name "Net-(JP5-VCC)") (class "Default")
      (node (ref "JP3") (pin "2") (pinfunction "2_2") (pintype "passive"))
      (node (ref "JP5") (pin "P$4") (pinfunction "VCC_P$4") (pintype "bidirectional"))
    )
    (net (code "39") (name "Net-(LED1-PadA)") (class "Default")
      (node (ref "LED1") (pin "A") (pinfunction "A_A") (pintype "passive"))
      (node (ref "R1") (pin "1") (pinfunction "1_1") (pintype "passive"))
    )
    (net (code "40") (name "Net-(LED2-PadA)") (class "Default")
      (node (ref "LED2") (pin "A") (pinfunction "A_A") (pintype "passive"))
      (node (ref "R2") (pin "1") (pinfunction "1_1") (pintype "passive"))
    )
    (net (code "41") (name "Net-(LED3-PadA)") (class "Default")
      (node (ref "LED3") (pin "A") (pinfunction "A_A") (pintype "passive"))
      (node (ref "R3") (pin "1") (pinfunction "1_1") (pintype "passive"))
    )
    (net (code "42") (name "Net-(LED4-PadC)") (class "Default")
      (node (ref "LED4") (pin "C") (pinfunction "C_C") (pintype "passive"))
      (node (ref "R8") (pin "2") (pinfunction "2_2") (pintype "passive"))
    )
    (net (code "43") (name "Net-(LED5-PadA)") (class "Default")
      (node (ref "LED5") (pin "A") (pinfunction "A_A") (pintype "passive"))
      (node (ref "R10") (pin "1") (pinfunction "1_1") (pintype "passive"))
    )
    (net (code "44") (name "Net-(LED6-PadA)") (class "Default")
      (node (ref "LED6") (pin "A") (pinfunction "A_A") (pintype "passive"))
      (node (ref "R11") (pin "1") (pinfunction "1_1") (pintype "passive"))
    )
    (net (code "45") (name "Net-(LED7-PadA)") (class "Default")
      (node (ref "LED7") (pin "A") (pinfunction "A_A") (pintype "passive"))
      (node (ref "R12") (pin "1") (pinfunction "1_1") (pintype "passive"))
    )
    (net (code "46") (name "Net-(LED8-PadC)") (class "Default")
      (node (ref "LED8") (pin "C") (pinfunction "C_C") (pintype "passive"))
      (node (ref "R15") (pin "2") (pinfunction "2_2") (pintype "passive"))
    )
    (net (code "47") (name "Net-(LED9-PadC)") (class "Default")
      (node (ref "LED9") (pin "C") (pinfunction "C_C") (pintype "passive"))
      (node (ref "R17") (pin "2") (pinfunction "2_2") (pintype "passive"))
    )
    (net (code "48") (name "Net-(LED10-PadC)") (class "Default")
      (node (ref "LED10") (pin "C") (pinfunction "C_C") (pintype "passive"))
      (node (ref "R26") (pin "1") (pinfunction "1_1") (pintype "passive"))
    )
    (net (code "49") (name "Net-(Q1A-DRAIN)") (class "Default")
      (node (ref "Q1") (pin "6") (pinfunction "DRAIN_6") (pintype "bidirectional"))
      (node (ref "Q2") (pin "1") (pinfunction "G_1") (pintype "passive"))
      (node (ref "R18") (pin "1") (pinfunction "1_1") (pintype "passive"))
    )
    (net (code "50") (name "Net-(Q1A-GATE)") (class "Default")
      (node (ref "Q1") (pin "2") (pinfunction "GATE_2") (pintype "bidirectional"))
      (node (ref "Q1") (pin "5") (pinfunction "GATE_5") (pintype "bidirectional"))
      (node (ref "R16") (pin "1") (pinfunction "1_1") (pintype "passive"))
    )
    (net (code "51") (name "Net-(Q1B-DRAIN)") (class "Default")
      (node (ref "Q1") (pin "3") (pinfunction "DRAIN_3") (pintype "bidirectional"))
      (node (ref "Q3") (pin "1") (pinfunction "G_1") (pintype "passive"))
      (node (ref "R21") (pin "1") (pinfunction "1_1") (pintype "passive"))
    )
    (net (code "52") (name "Net-(Q2-D)") (class "Default")
      (node (ref "Q2") (pin "3") (pinfunction "D_3") (pintype "passive"))
      (node (ref "R19") (pin "2") (pinfunction "2_2") (pintype "passive"))
    )
    (net (code "53") (name "Net-(Q3-D)") (class "Default")
      (node (ref "Q3") (pin "3") (pinfunction "D_3") (pintype "passive"))
      (node (ref "R22") (pin "2") (pinfunction "2_2") (pintype "passive"))
    )
    (net (code "54") (name "Net-(Q4A-GATE)") (class "Default")
      (node (ref "Q4") (pin "2") (pinfunction "GATE_2") (pintype "bidirectional"))
      (node (ref "R27") (pin "2") (pinfunction "2_2") (pintype "passive"))
      (node (ref "R28") (pin "1") (pinfunction "1_1") (pintype "passive"))
      (node (ref "U3") (pin "4") (pinfunction "4_4") (pintype "bidirectional"))
    )
    (net (code "55") (name "Net-(Q4B-DRAIN)") (class "Default")
      (node (ref "Q4") (pin "3") (pinfunction "DRAIN_3") (pintype "bidirectional"))
      (node (ref "R26") (pin "2") (pinfunction "2_2") (pintype "passive"))
    )
    (net (code "56") (name "Net-(R24-Pad1)") (class "Default")
      (node (ref "R24") (pin "1") (pinfunction "1_1") (pintype "passive"))
      (node (ref "U3") (pin "1") (pinfunction "1_1") (pintype "bidirectional"))
    )
    (net (code "57") (name "Net-(U1-AVCC1)") (class "Default")
      (node (ref "C5") (pin "1") (pinfunction "1_1") (pintype "passive"))
      (node (ref "R4") (pin "1") (pinfunction "1_1") (pintype "passive"))
      (node (ref "U1") (pin "11") (pinfunction "AVCC1_11") (pintype "bidirectional"))
    )
    (net (code "58") (name "Net-(U1-PUR)") (class "Default")
      (node (ref "R5") (pin "2") (pinfunction "2_2") (pintype "passive"))
      (node (ref "U1") (pin "63") (pinfunction "PUR_63") (pintype "bidirectional"))
    )
    (net (code "59") (name "Net-(U1-V18)") (class "Default")
      (node (ref "C7") (pin "1") (pinfunction "1_1") (pintype "passive"))
      (node (ref "U1") (pin "67") (pinfunction "V18_67") (pintype "bidirectional"))
    )
    (net (code "60") (name "Net-(U1-VCORE)") (class "Default")
      (node (ref "C4") (pin "1") (pinfunction "1_1") (pintype "passive"))
      (node (ref "U1") (pin "20") (pinfunction "VCORE_20") (pintype "bidirectional"))
    )
    (net (code "61") (name "Net-(U1-VUSB)") (class "Default")
      (node (ref "C6") (pin "1") (pinfunction "1_1") (pintype "passive"))
      (node (ref "U1") (pin "66") (pinfunction "VUSB_66") (pintype "bidirectional"))
    )
    (net (code "62") (name "Net-(U2-3V3OUT)") (class "Default")
      (node (ref "C12") (pin "1") (pinfunction "1_1") (pintype "passive"))
      (node (ref "U2") (pin "17") (pinfunction "3V3OUT_17") (pintype "output"))
    )
    (net (code "63") (name "Net-(U2-RXLED)") (class "Default")
      (node (ref "R17") (pin "1") (pinfunction "1_1") (pintype "passive"))
      (node (ref "U2") (pin "22") (pinfunction "RXLED_22") (pintype "input"))
    )
    (net (code "64") (name "Net-(U2-TXLED)") (class "Default")
      (node (ref "R15") (pin "1") (pinfunction "1_1") (pintype "passive"))
      (node (ref "U2") (pin "23") (pinfunction "TXLED_23") (pintype "input"))
    )
    (net (code "65") (name "Net-(U2-USBDM)") (class "Default")
      (node (ref "JP7") (pin "D-") (pinfunction "D-_D-") (pintype "bidirectional"))
      (node (ref "U2") (pin "16") (pinfunction "USBDM_16") (pintype "bidirectional"))
    )
    (net (code "66") (name "Net-(U2-USBDP)") (class "Default")
      (node (ref "JP7") (pin "D+") (pinfunction "D+_D+") (pintype "bidirectional"))
      (node (ref "U2") (pin "15") (pinfunction "USBDP_15") (pintype "bidirectional"))
    )
    (net (code "67") (name "RXI") (class "Default")
      (node (ref "JP5") (pin "P$3") (pinfunction "RXI_P$3") (pintype "bidirectional"))
      (node (ref "SJ2") (pin "2") (pinfunction "2_2") (pintype "passive"))
    )
    (net (code "68") (name "SBWTCK") (class "Default")
      (node (ref "JP4") (pin "7") (pinfunction "7_7") (pintype "bidirectional"))
      (node (ref "U1") (pin "71") (pinfunction "TEST/SBWTCK_71") (pintype "bidirectional"))
    )
    (net (code "69") (name "SBWTDIO") (class "Default")
      (node (ref "C8") (pin "1") (pinfunction "1_1") (pintype "passive"))
      (node (ref "JP4") (pin "1") (pinfunction "1_1") (pintype "bidirectional"))
      (node (ref "R6") (pin "1") (pinfunction "1_1") (pintype "passive"))
      (node (ref "S1") (pin "2") (pinfunction "2_2") (pintype "bidirectional"))
      (node (ref "U1") (pin "76") (pinfunction "/RST/NMI/SBWTDIO_76") (pintype "bidirectional"))
    )
    (net (code "70") (name "STAT_ERR") (class "Default")
      (node (ref "R12") (pin "2") (pinfunction "2_2") (pintype "passive"))
      (node (ref "U1") (pin "54") (pinfunction "P4.7/PM_NONE_54") (pintype "bidirectional"))
    )
    (net (code "71") (name "STAT_OK") (class "Default")
      (node (ref "R10") (pin "2") (pinfunction "2_2") (pintype "passive"))
      (node (ref "U1") (pin "56") (pinfunction "P5.7/TB0.1_56") (pintype "bidirectional"))
    )
    (net (code "72") (name "STAT_WARN") (class "Default")
      (node (ref "R11") (pin "2") (pinfunction "2_2") (pintype "passive"))
      (node (ref "U1") (pin "55") (pinfunction "P5.6/TB0.0_55") (pintype "bidirectional"))
    )
    (net (code "73") (name "TXO") (class "Default")
      (node (ref "JP5") (pin "P$2") (pinfunction "TXO_P$2") (pintype "bidirectional"))
      (node (ref "SJ1") (pin "2") (pinfunction "2_2") (pintype "passive"))
    )
    (net (code "74") (name "USB_RX") (class "Default")
      (node (ref "JP10") (pin "3") (pinfunction "3_3") (pintype "passive"))
      (node (ref "SJ3") (pin "2") (pinfunction "2_2") (pintype "passive"))
      (node (ref "U2") (pin "1") (pinfunction "TXD_1") (pintype "output"))
    )
    (net (code "75") (name "USB_RXD") (class "Default")
      (node (ref "R13") (pin "2") (pinfunction "2_2") (pintype "passive"))
      (node (ref "SJ3") (pin "3") (pinfunction "3_3") (pintype "passive"))
      (node (ref "SJ4") (pin "1") (pinfunction "1_1") (pintype "passive"))
      (node (ref "U1") (pin "52") (pinfunction "P4.5/PM_UCA1RXD/PM_UCA1SOMI_52") (pintype "bidirectional"))
    )
    (net (code "76") (name "USB_TX") (class "Default")
      (node (ref "JP10") (pin "2") (pinfunction "2_2") (pintype "passive"))
      (node (ref "SJ4") (pin "2") (pinfunction "2_2") (pintype "passive"))
      (node (ref "U2") (pin "5") (pinfunction "RXD_5") (pintype "input"))
    )
    (net (code "77") (name "USB_TXD") (class "Default")
      (node (ref "R14") (pin "2") (pinfunction "2_2") (pintype "passive"))
      (node (ref "SJ3") (pin "1") (pinfunction "1_1") (pintype "passive"))
      (node (ref "SJ4") (pin "3") (pinfunction "3_3") (pintype "passive"))
      (node (ref "U1") (pin "51") (pinfunction "P4.4/PM_UCA1TXD/PM_UCA1SIMO_51") (pintype "bidirectional"))
    )
    (net (code "78") (name "VBUS") (class "Default")
      (node (ref "C11") (pin "1") (pinfunction "1_1") (pintype "passive"))
      (node (ref "JP7") (pin "VBUS") (pinfunction "VBUS_VBUS") (pintype "bidirectional"))
      (node (ref "LED8") (pin "A") (pinfunction "A_A") (pintype "passive"))
      (node (ref "LED9") (pin "A") (pinfunction "A_A") (pintype "passive"))
      (node (ref "U2") (pin "20") (pinfunction "VCC_20") (pintype "power_in"))
      (node (ref "U2") (pin "4") (pinfunction "VCCIO_4") (pintype "power_in"))
    )
    (net (code "79") (name "VCC_TARGET") (class "Default")
      (node (ref "JP4") (pin "4") (pinfunction "4_4") (pintype "bidirectional"))
      (node (ref "JP6") (pin "1") (pinfunction "1_1") (pintype "passive"))
    )
    (net (code "80") (name "VCC_TOOL") (class "Default")
      (node (ref "JP4") (pin "2") (pinfunction "2_2") (pintype "bidirectional"))
      (node (ref "JP6") (pin "3") (pinfunction "3_3") (pintype "passive"))
    )
    (net (code "81") (name "XT2IN") (class "Default")
      (node (ref "C9") (pin "1") (pinfunction "1_1") (pintype "passive"))
      (node (ref "U1") (pin "69") (pinfunction "P5.2/XT2IN_69") (pintype "bidirectional"))
      (node (ref "Y1") (pin "1") (pinfunction "1_1") (pintype "passive"))
    )
    (net (code "82") (name "XT2OUT") (class "Default")
      (node (ref "C10") (pin "1") (pinfunction "1_1") (pintype "passive"))
      (node (ref "U1") (pin "70") (pinfunction "P5.3/XT2OUT_70") (pintype "bidirectional"))
      (node (ref "Y1") (pin "2") (pinfunction "2_2") (pintype "passive"))
    )
    (net (code "83") (name "unconnected-(JP4-Pad3)") (class "Default")
      (node (ref "JP4") (pin "3") (pinfunction "3_3") (pintype "bidirectional"))
    )
    (net (code "84") (name "unconnected-(JP4-Pad5)") (class "Default")
      (node (ref "JP4") (pin "5") (pinfunction "5_5") (pintype "bidirectional"))
    )
    (net (code "85") (name "unconnected-(JP4-Pad6)") (class "Default")
      (node (ref "JP4") (pin "6") (pinfunction "6_6") (pintype "bidirectional"))
    )
    (net (code "86") (name "unconnected-(JP4-Pad8)") (class "Default")
      (node (ref "JP4") (pin "8") (pinfunction "8_8") (pintype "bidirectional"))
    )
    (net (code "87") (name "unconnected-(JP4-Pad10)") (class "Default")
      (node (ref "JP4") (pin "10") (pinfunction "10_10") (pintype "bidirectional"))
    )
    (net (code "88") (name "unconnected-(JP4-Pad11)") (class "Default")
      (node (ref "JP4") (pin "11") (pinfunction "11_11") (pintype "bidirectional"))
    )
    (net (code "89") (name "unconnected-(JP4-Pad12)") (class "Default")
      (node (ref "JP4") (pin "12") (pinfunction "12_12") (pintype "bidirectional"))
    )
    (net (code "90") (name "unconnected-(JP4-Pad13)") (class "Default")
      (node (ref "JP4") (pin "13") (pinfunction "13_13") (pintype "bidirectional"))
    )
    (net (code "91") (name "unconnected-(JP4-Pad14)") (class "Default")
      (node (ref "JP4") (pin "14") (pinfunction "14_14") (pintype "bidirectional"))
    )
    (net (code "92") (name "unconnected-(JP5-CTS-PadP$5)") (class "Default")
      (node (ref "JP5") (pin "P$5") (pinfunction "CTS_P$5") (pintype "bidirectional"))
    )
    (net (code "93") (name "unconnected-(JP5-DTR-PadP$1)") (class "Default")
      (node (ref "JP5") (pin "P$1") (pinfunction "DTR_P$1") (pintype "bidirectional"))
    )
    (net (code "94") (name "unconnected-(U1-P1.1{slash}TA0.0-Pad22)") (class "Default")
      (node (ref "U1") (pin "22") (pinfunction "P1.1/TA0.0_22") (pintype "bidirectional"))
    )
    (net (code "95") (name "unconnected-(U1-P1.2{slash}TA0.1-Pad23)") (class "Default")
      (node (ref "U1") (pin "23") (pinfunction "P1.2/TA0.1_23") (pintype "bidirectional"))
    )
    (net (code "96") (name "unconnected-(U1-P1.3{slash}TA0.2-Pad24)") (class "Default")
      (node (ref "U1") (pin "24") (pinfunction "P1.3/TA0.2_24") (pintype "bidirectional"))
    )
    (net (code "97") (name "unconnected-(U1-P1.5{slash}TA0.4-Pad26)") (class "Default")
      (node (ref "U1") (pin "26") (pinfunction "P1.5/TA0.4_26") (pintype "bidirectional"))
    )
    (net (code "98") (name "unconnected-(U1-P1.6{slash}TA1CLK{slash}CBOUT-Pad27)") (class "Default")
      (node (ref "U1") (pin "27") (pinfunction "P1.6/TA1CLK/CBOUT_27") (pintype "bidirectional"))
    )
    (net (code "99") (name "unconnected-(U1-P1.7{slash}TA1.0-Pad28)") (class "Default")
      (node (ref "U1") (pin "28") (pinfunction "P1.7/TA1.0_28") (pintype "bidirectional"))
    )
    (net (code "100") (name "unconnected-(U1-P2.0{slash}TA1.1-Pad29)") (class "Default")
      (node (ref "U1") (pin "29") (pinfunction "P2.0/TA1.1_29") (pintype "bidirectional"))
    )
    (net (code "101") (name "unconnected-(U1-P2.1{slash}TA1.2-Pad30)") (class "Default")
      (node (ref "U1") (pin "30") (pinfunction "P2.1/TA1.2_30") (pintype "bidirectional"))
    )
    (net (code "102") (name "unconnected-(U1-P3.5{slash}TB0.5-Pad42)") (class "Default")
      (node (ref "U1") (pin "42") (pinfunction "P3.5/TB0.5_42") (pintype "bidirectional"))
    )
    (net (code "103") (name "unconnected-(U1-P3.6{slash}TB0.6-Pad43)") (class "Default")
      (node (ref "U1") (pin "43") (pinfunction "P3.6/TB0.6_43") (pintype "bidirectional"))
    )
    (net (code "104") (name "unconnected-(U1-P4.6{slash}PM_NONE-Pad53)") (class "Default")
      (node (ref "U1") (pin "53") (pinfunction "P4.6/PM_NONE_53") (pintype "bidirectional"))
    )
    (net (code "105") (name "unconnected-(U1-P5.4{slash}XIN-Pad12)") (class "Default")
      (node (ref "U1") (pin "12") (pinfunction "P5.4/XIN_12") (pintype "bidirectional"))
    )
    (net (code "106") (name "unconnected-(U1-P5.5{slash}XOUT-Pad13)") (class "Default")
      (node (ref "U1") (pin "13") (pinfunction "P5.5/XOUT_13") (pintype "bidirectional"))
    )
    (net (code "107") (name "unconnected-(U1-P6.0{slash}CB0{slash}A0-Pad77)") (class "Default")
      (node (ref "U1") (pin "77") (pinfunction "P6.0/CB0/A0_77") (pintype "bidirectional"))
    )
    (net (code "108") (name "unconnected-(U1-P6.1{slash}CB1{slash}A1-Pad78)") (class "Default")
      (node (ref "U1") (pin "78") (pinfunction "P6.1/CB1/A1_78") (pintype "bidirectional"))
    )
    (net (code "109") (name "unconnected-(U1-P6.2{slash}CB2{slash}A2-Pad79)") (class "Default")
      (node (ref "U1") (pin "79") (pinfunction "P6.2/CB2/A2_79") (pintype "bidirectional"))
    )
    (net (code "110") (name "unconnected-(U1-P7.1{slash}CB9{slash}A13-Pad6)") (class "Default")
      (node (ref "U1") (pin "6") (pinfunction "P7.1/CB9/A13_6") (pintype "bidirectional"))
    )
    (net (code "111") (name "unconnected-(U1-P7.2{slash}CB10{slash}A14-Pad7)") (class "Default")
      (node (ref "U1") (pin "7") (pinfunction "P7.2/CB10/A14_7") (pintype "bidirectional"))
    )
    (net (code "112") (name "unconnected-(U1-P7.3{slash}CB11{slash}A15-Pad8)") (class "Default")
      (node (ref "U1") (pin "8") (pinfunction "P7.3/CB11/A15_8") (pintype "bidirectional"))
    )
    (net (code "113") (name "unconnected-(U1-P7.4{slash}TB0.2-Pad57)") (class "Default")
      (node (ref "U1") (pin "57") (pinfunction "P7.4/TB0.2_57") (pintype "bidirectional"))
    )
    (net (code "114") (name "unconnected-(U1-P7.5{slash}TB0.3-Pad58)") (class "Default")
      (node (ref "U1") (pin "58") (pinfunction "P7.5/TB0.3_58") (pintype "bidirectional"))
    )
    (net (code "115") (name "unconnected-(U1-P7.6{slash}TB0.4-Pad59)") (class "Default")
      (node (ref "U1") (pin "59") (pinfunction "P7.6/TB0.4_59") (pintype "bidirectional"))
    )
    (net (code "116") (name "unconnected-(U1-P8.0-Pad15)") (class "Default")
      (node (ref "U1") (pin "15") (pinfunction "P8.0_15") (pintype "bidirectional"))
    )
    (net (code "117") (name "unconnected-(U1-P8.1-Pad16)") (class "Default")
      (node (ref "U1") (pin "16") (pinfunction "P8.1_16") (pintype "bidirectional"))
    )
    (net (code "118") (name "unconnected-(U1-P8.2-Pad17)") (class "Default")
      (node (ref "U1") (pin "17") (pinfunction "P8.2_17") (pintype "bidirectional"))
    )
    (net (code "119") (name "unconnected-(U1-PJ.0{slash}TDO-Pad72)") (class "Default")
      (node (ref "U1") (pin "72") (pinfunction "PJ.0/TDO_72") (pintype "bidirectional"))
    )
    (net (code "120") (name "unconnected-(U1-PJ.1{slash}TDI{slash}TCK-Pad73)") (class "Default")
      (node (ref "U1") (pin "73") (pinfunction "PJ.1/TDI/TCK_73") (pintype "bidirectional"))
    )
    (net (code "121") (name "unconnected-(U1-PJ.2{slash}TMS-Pad74)") (class "Default")
      (node (ref "U1") (pin "74") (pinfunction "PJ.2/TMS_74") (pintype "bidirectional"))
    )
    (net (code "122") (name "unconnected-(U1-PJ.3{slash}TCK-Pad75)") (class "Default")
      (node (ref "U1") (pin "75") (pinfunction "PJ.3/TCK_75") (pintype "bidirectional"))
    )
    (net (code "123") (name "unconnected-(U1-PU.0{slash}DP-Pad62)") (class "Default")
      (node (ref "U1") (pin "62") (pinfunction "PU.0/DP_62") (pintype "bidirectional"))
    )
    (net (code "124") (name "unconnected-(U1-PU.1{slash}DM-Pad64)") (class "Default")
      (node (ref "U1") (pin "64") (pinfunction "PU.1/DM_64") (pintype "bidirectional"))
    )
    (net (code "125") (name "unconnected-(U1-VBUS-Pad65)") (class "Default")
      (node (ref "U1") (pin "65") (pinfunction "VBUS_65") (pintype "bidirectional"))
    )
    (net (code "126") (name "unconnected-(U2-CTS-Pad11)") (class "Default")
      (node (ref "U2") (pin "11") (pinfunction "CTS_11") (pintype "input"))
    )
    (net (code "127") (name "unconnected-(U2-DCD-Pad10)") (class "Default")
      (node (ref "U2") (pin "10") (pinfunction "DCD_10") (pintype "input"))
    )
    (net (code "128") (name "unconnected-(U2-DSR-Pad9)") (class "Default")
      (node (ref "U2") (pin "9") (pinfunction "DSR_9") (pintype "input"))
    )
    (net (code "129") (name "unconnected-(U2-DTR-Pad2)") (class "Default")
      (node (ref "U2") (pin "2") (pinfunction "DTR_2") (pintype "output"))
    )
    (net (code "130") (name "unconnected-(U2-OSCI-Pad27)") (class "Default")
      (node (ref "U2") (pin "27") (pinfunction "OSCI_27") (pintype "input"))
    )
    (net (code "131") (name "unconnected-(U2-OSCO-Pad28)") (class "Default")
      (node (ref "U2") (pin "28") (pinfunction "OSCO_28") (pintype "output"))
    )
    (net (code "132") (name "unconnected-(U2-PWREN-Pad14)") (class "Default")
      (node (ref "U2") (pin "14") (pinfunction "PWREN_14") (pintype "input"))
    )
    (net (code "133") (name "unconnected-(U2-RESET-Pad19)") (class "Default")
      (node (ref "U2") (pin "19") (pinfunction "RESET_19") (pintype "input"))
    )
    (net (code "134") (name "unconnected-(U2-RI-Pad6)") (class "Default")
      (node (ref "U2") (pin "6") (pinfunction "RI_6") (pintype "input"))
    )
    (net (code "135") (name "unconnected-(U2-RTS-Pad3)") (class "Default")
      (node (ref "U2") (pin "3") (pinfunction "RTS_3") (pintype "output"))
    )
    (net (code "136") (name "unconnected-(U2-SLEEP-Pad12)") (class "Default")
      (node (ref "U2") (pin "12") (pinfunction "SLEEP_12") (pintype "input"))
    )
    (net (code "137") (name "unconnected-(U2-TXDEN-Pad13)") (class "Default")
      (node (ref "U2") (pin "13") (pinfunction "TXDEN_13") (pintype "input"))
    )
  )
)
